# CNT_1_1.net
KiCad netlist of a schematic drawn in EAGLE
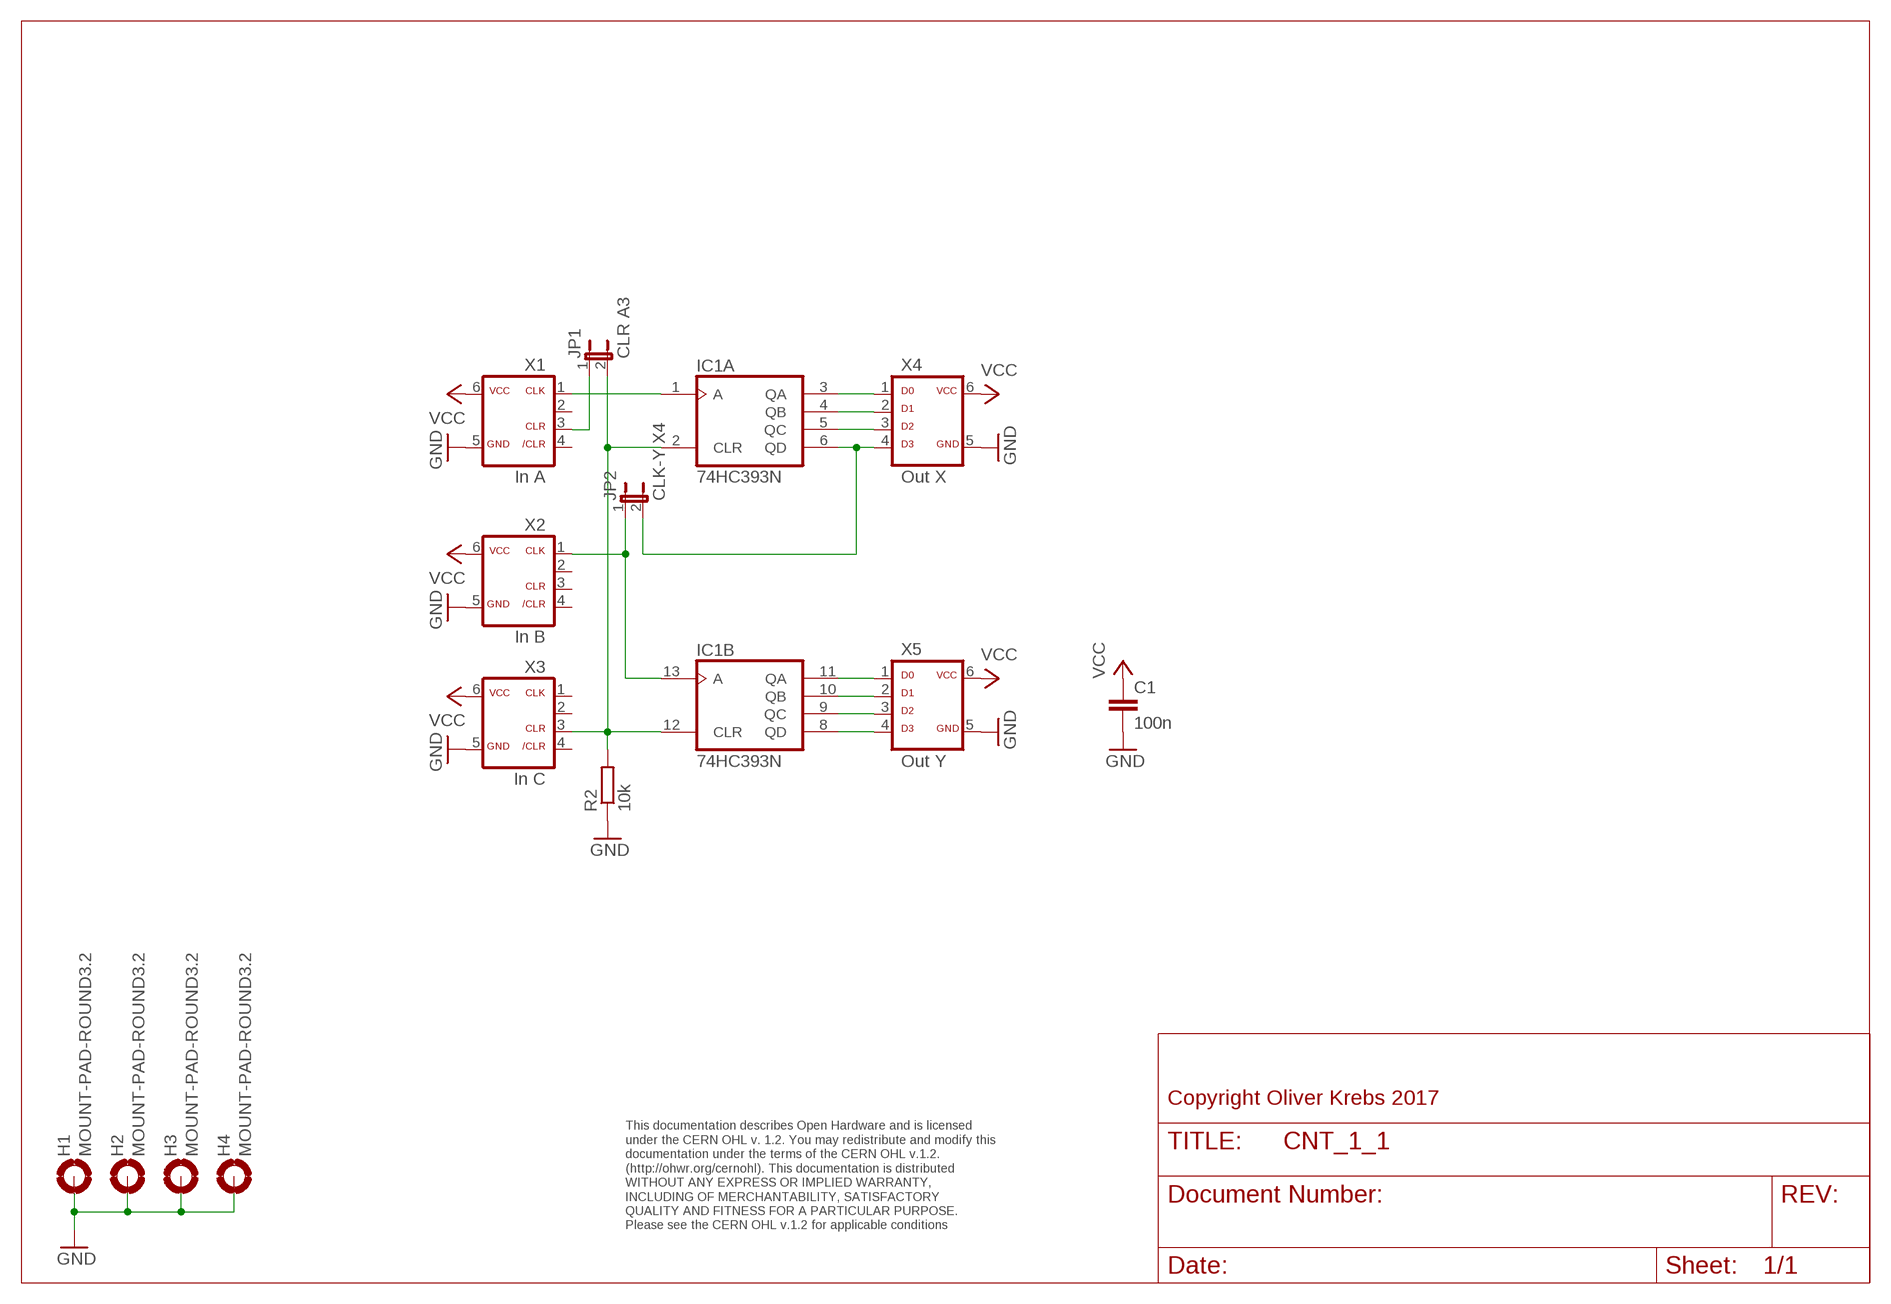
[diagram p0: schematic, sheet 1]

(export (version "E")
  (design (tool "Eeschema 10.0.6"))
  (components
    (comp (ref "C1")
      (value "100n")
      (footprint "eagle-import:C050-025X075")
      (libsource (lib "eagle-import") (part "C-EU050-025X075"))
    )
    (comp (ref "H1")
      (value "MOUNT-PAD-ROUND3.2")
      (footprint "eagle-import:3,2-PAD")
      (libsource (lib "eagle-import") (part "MOUNT-PAD-ROUND3.2"))
    )
    (comp (ref "H2")
      (value "MOUNT-PAD-ROUND3.2")
      (footprint "eagle-import:3,2-PAD")
      (libsource (lib "eagle-import") (part "MOUNT-PAD-ROUND3.2"))
    )
    (comp (ref "H3")
      (value "MOUNT-PAD-ROUND3.2")
      (footprint "eagle-import:3,2-PAD")
      (libsource (lib "eagle-import") (part "MOUNT-PAD-ROUND3.2"))
    )
    (comp (ref "H4")
      (value "MOUNT-PAD-ROUND3.2")
      (footprint "eagle-import:3,2-PAD")
      (libsource (lib "eagle-import") (part "MOUNT-PAD-ROUND3.2"))
    )
    (comp (ref "IC1")
      (value "74HC393N")
      (footprint "eagle-import:DIL14")
      (libsource (lib "eagle-import") (part "74393NHC"))
    )
    (comp (ref "JP1")
      (value "CLR A3")
      (footprint "eagle-import:JP1")
      (libsource (lib "eagle-import") (part "JP1E"))
    )
    (comp (ref "JP2")
      (value "CLK-Y X4")
      (footprint "eagle-import:JP1")
      (libsource (lib "eagle-import") (part "JP1E"))
    )
    (comp (ref "R2")
      (value "10k")
      (footprint "eagle-import:0207_10")
      (libsource (lib "eagle-import") (part "R-EU_0207/10"))
    )
    (comp (ref "X1")
      (value "In A")
      (footprint "eagle-import:ML-6")
      (libsource (lib "eagle-import") (part "ML6C"))
    )
    (comp (ref "X2")
      (value "In B")
      (footprint "eagle-import:ML-6")
      (libsource (lib "eagle-import") (part "ML6C"))
    )
    (comp (ref "X3")
      (value "In C")
      (footprint "eagle-import:ML-6")
      (libsource (lib "eagle-import") (part "ML6C"))
    )
    (comp (ref "X4")
      (value "Out X")
      (footprint "eagle-import:ML-6")
      (libsource (lib "eagle-import") (part "ML6D"))
    )
    (comp (ref "X5")
      (value "Out Y")
      (footprint "eagle-import:ML-6")
      (libsource (lib "eagle-import") (part "ML6D"))
    )
  )
  (nets
    (net (code "1") (name "GND") (class "Default")
      (node (ref "C1") (pin "2") (pinfunction "2_2") (pintype "passive"))
      (node (ref "H1") (pin "B3,2") (pinfunction "MOUNT_B3,2") (pintype "passive"))
      (node (ref "H2") (pin "B3,2") (pinfunction "MOUNT_B3,2") (pintype "passive"))
      (node (ref "H3") (pin "B3,2") (pinfunction "MOUNT_B3,2") (pintype "passive"))
      (node (ref "H4") (pin "B3,2") (pinfunction "MOUNT_B3,2") (pintype "passive"))
      (node (ref "R2") (pin "1") (pinfunction "1_1") (pintype "passive"))
      (node (ref "X1") (pin "5") (pinfunction "5_5") (pintype "passive"))
      (node (ref "X2") (pin "5") (pinfunction "5_5") (pintype "passive"))
      (node (ref "X3") (pin "5") (pinfunction "5_5") (pintype "passive"))
      (node (ref "X4") (pin "5") (pinfunction "5_5") (pintype "passive"))
      (node (ref "X5") (pin "5") (pinfunction "5_5") (pintype "passive"))
    )
    (net (code "2") (name "Net-(IC1A-A)") (class "Default")
      (node (ref "IC1") (pin "1") (pinfunction "A_1") (pintype "input"))
      (node (ref "X1") (pin "1") (pinfunction "1_1") (pintype "passive"))
    )
    (net (code "3") (name "Net-(IC1A-CLR)") (class "Default")
      (node (ref "IC1") (pin "12") (pinfunction "CLR_12") (pintype "input"))
      (node (ref "IC1") (pin "2") (pinfunction "CLR_2") (pintype "input"))
      (node (ref "JP1") (pin "2") (pinfunction "2_2") (pintype "passive"))
      (node (ref "R2") (pin "2") (pinfunction "2_2") (pintype "passive"))
      (node (ref "X3") (pin "3") (pinfunction "3_3") (pintype "passive"))
    )
    (net (code "4") (name "Net-(IC1A-QA)") (class "Default")
      (node (ref "IC1") (pin "3") (pinfunction "QA_3") (pintype "output"))
      (node (ref "X4") (pin "1") (pinfunction "1_1") (pintype "passive"))
    )
    (net (code "5") (name "Net-(IC1A-QB)") (class "Default")
      (node (ref "IC1") (pin "4") (pinfunction "QB_4") (pintype "output"))
      (node (ref "X4") (pin "2") (pinfunction "2_2") (pintype "passive"))
    )
    (net (code "6") (name "Net-(IC1A-QC)") (class "Default")
      (node (ref "IC1") (pin "5") (pinfunction "QC_5") (pintype "output"))
      (node (ref "X4") (pin "3") (pinfunction "3_3") (pintype "passive"))
    )
    (net (code "7") (name "Net-(IC1A-QD)") (class "Default")
      (node (ref "IC1") (pin "6") (pinfunction "QD_6") (pintype "output"))
      (node (ref "JP2") (pin "2") (pinfunction "2_2") (pintype "passive"))
      (node (ref "X4") (pin "4") (pinfunction "4_4") (pintype "passive"))
    )
    (net (code "8") (name "Net-(IC1B-A)") (class "Default")
      (node (ref "IC1") (pin "13") (pinfunction "A_13") (pintype "input"))
      (node (ref "JP2") (pin "1") (pinfunction "1_1") (pintype "passive"))
      (node (ref "X2") (pin "1") (pinfunction "1_1") (pintype "passive"))
    )
    (net (code "9") (name "Net-(IC1B-QA)") (class "Default")
      (node (ref "IC1") (pin "11") (pinfunction "QA_11") (pintype "output"))
      (node (ref "X5") (pin "1") (pinfunction "1_1") (pintype "passive"))
    )
    (net (code "10") (name "Net-(IC1B-QB)") (class "Default")
      (node (ref "IC1") (pin "10") (pinfunction "QB_10") (pintype "output"))
      (node (ref "X5") (pin "2") (pinfunction "2_2") (pintype "passive"))
    )
    (net (code "11") (name "Net-(IC1B-QC)") (class "Default")
      (node (ref "IC1") (pin "9") (pinfunction "QC_9") (pintype "output"))
      (node (ref "X5") (pin "3") (pinfunction "3_3") (pintype "passive"))
    )
    (net (code "12") (name "Net-(IC1B-QD)") (class "Default")
      (node (ref "IC1") (pin "8") (pinfunction "QD_8") (pintype "output"))
      (node (ref "X5") (pin "4") (pinfunction "4_4") (pintype "passive"))
    )
    (net (code "13") (name "Net-(JP1-Pad1)") (class "Default")
      (node (ref "JP1") (pin "1") (pinfunction "1_1") (pintype "passive"))
      (node (ref "X1") (pin "3") (pinfunction "3_3") (pintype "passive"))
    )
    (net (code "14") (name "VCC") (class "Default")
      (node (ref "C1") (pin "1") (pinfunction "1_1") (pintype "passive"))
      (node (ref "X1") (pin "6") (pinfunction "6_6") (pintype "passive"))
      (node (ref "X2") (pin "6") (pinfunction "6_6") (pintype "passive"))
      (node (ref "X3") (pin "6") (pinfunction "6_6") (pintype "passive"))
      (node (ref "X4") (pin "6") (pinfunction "6_6") (pintype "passive"))
      (node (ref "X5") (pin "6") (pinfunction "6_6") (pintype "passive"))
    )
    (net (code "15") (name "unconnected-(X1-Pad2)") (class "Default")
      (node (ref "X1") (pin "2") (pinfunction "2_2") (pintype "passive"))
    )
    (net (code "16") (name "unconnected-(X1-Pad4)") (class "Default")
      (node (ref "X1") (pin "4") (pinfunction "4_4") (pintype "passive"))
    )
    (net (code "17") (name "unconnected-(X2-Pad2)") (class "Default")
      (node (ref "X2") (pin "2") (pinfunction "2_2") (pintype "passive"))
    )
    (net (code "18") (name "unconnected-(X2-Pad3)") (class "Default")
      (node (ref "X2") (pin "3") (pinfunction "3_3") (pintype "passive"))
    )
    (net (code "19") (name "unconnected-(X2-Pad4)") (class "Default")
      (node (ref "X2") (pin "4") (pinfunction "4_4") (pintype "passive"))
    )
    (net (code "20") (name "unconnected-(X3-Pad1)") (class "Default")
      (node (ref "X3") (pin "1") (pinfunction "1_1") (pintype "passive"))
    )
    (net (code "21") (name "unconnected-(X3-Pad2)") (class "Default")
      (node (ref "X3") (pin "2") (pinfunction "2_2") (pintype "passive"))
    )
    (net (code "22") (name "unconnected-(X3-Pad4)") (class "Default")
      (node (ref "X3") (pin "4") (pinfunction "4_4") (pintype "passive"))
    )
  )
)
